# 12-MT7688AN_DDR2_I_F-B.net
KiCad netlist of a schematic drawn in Altium Designer
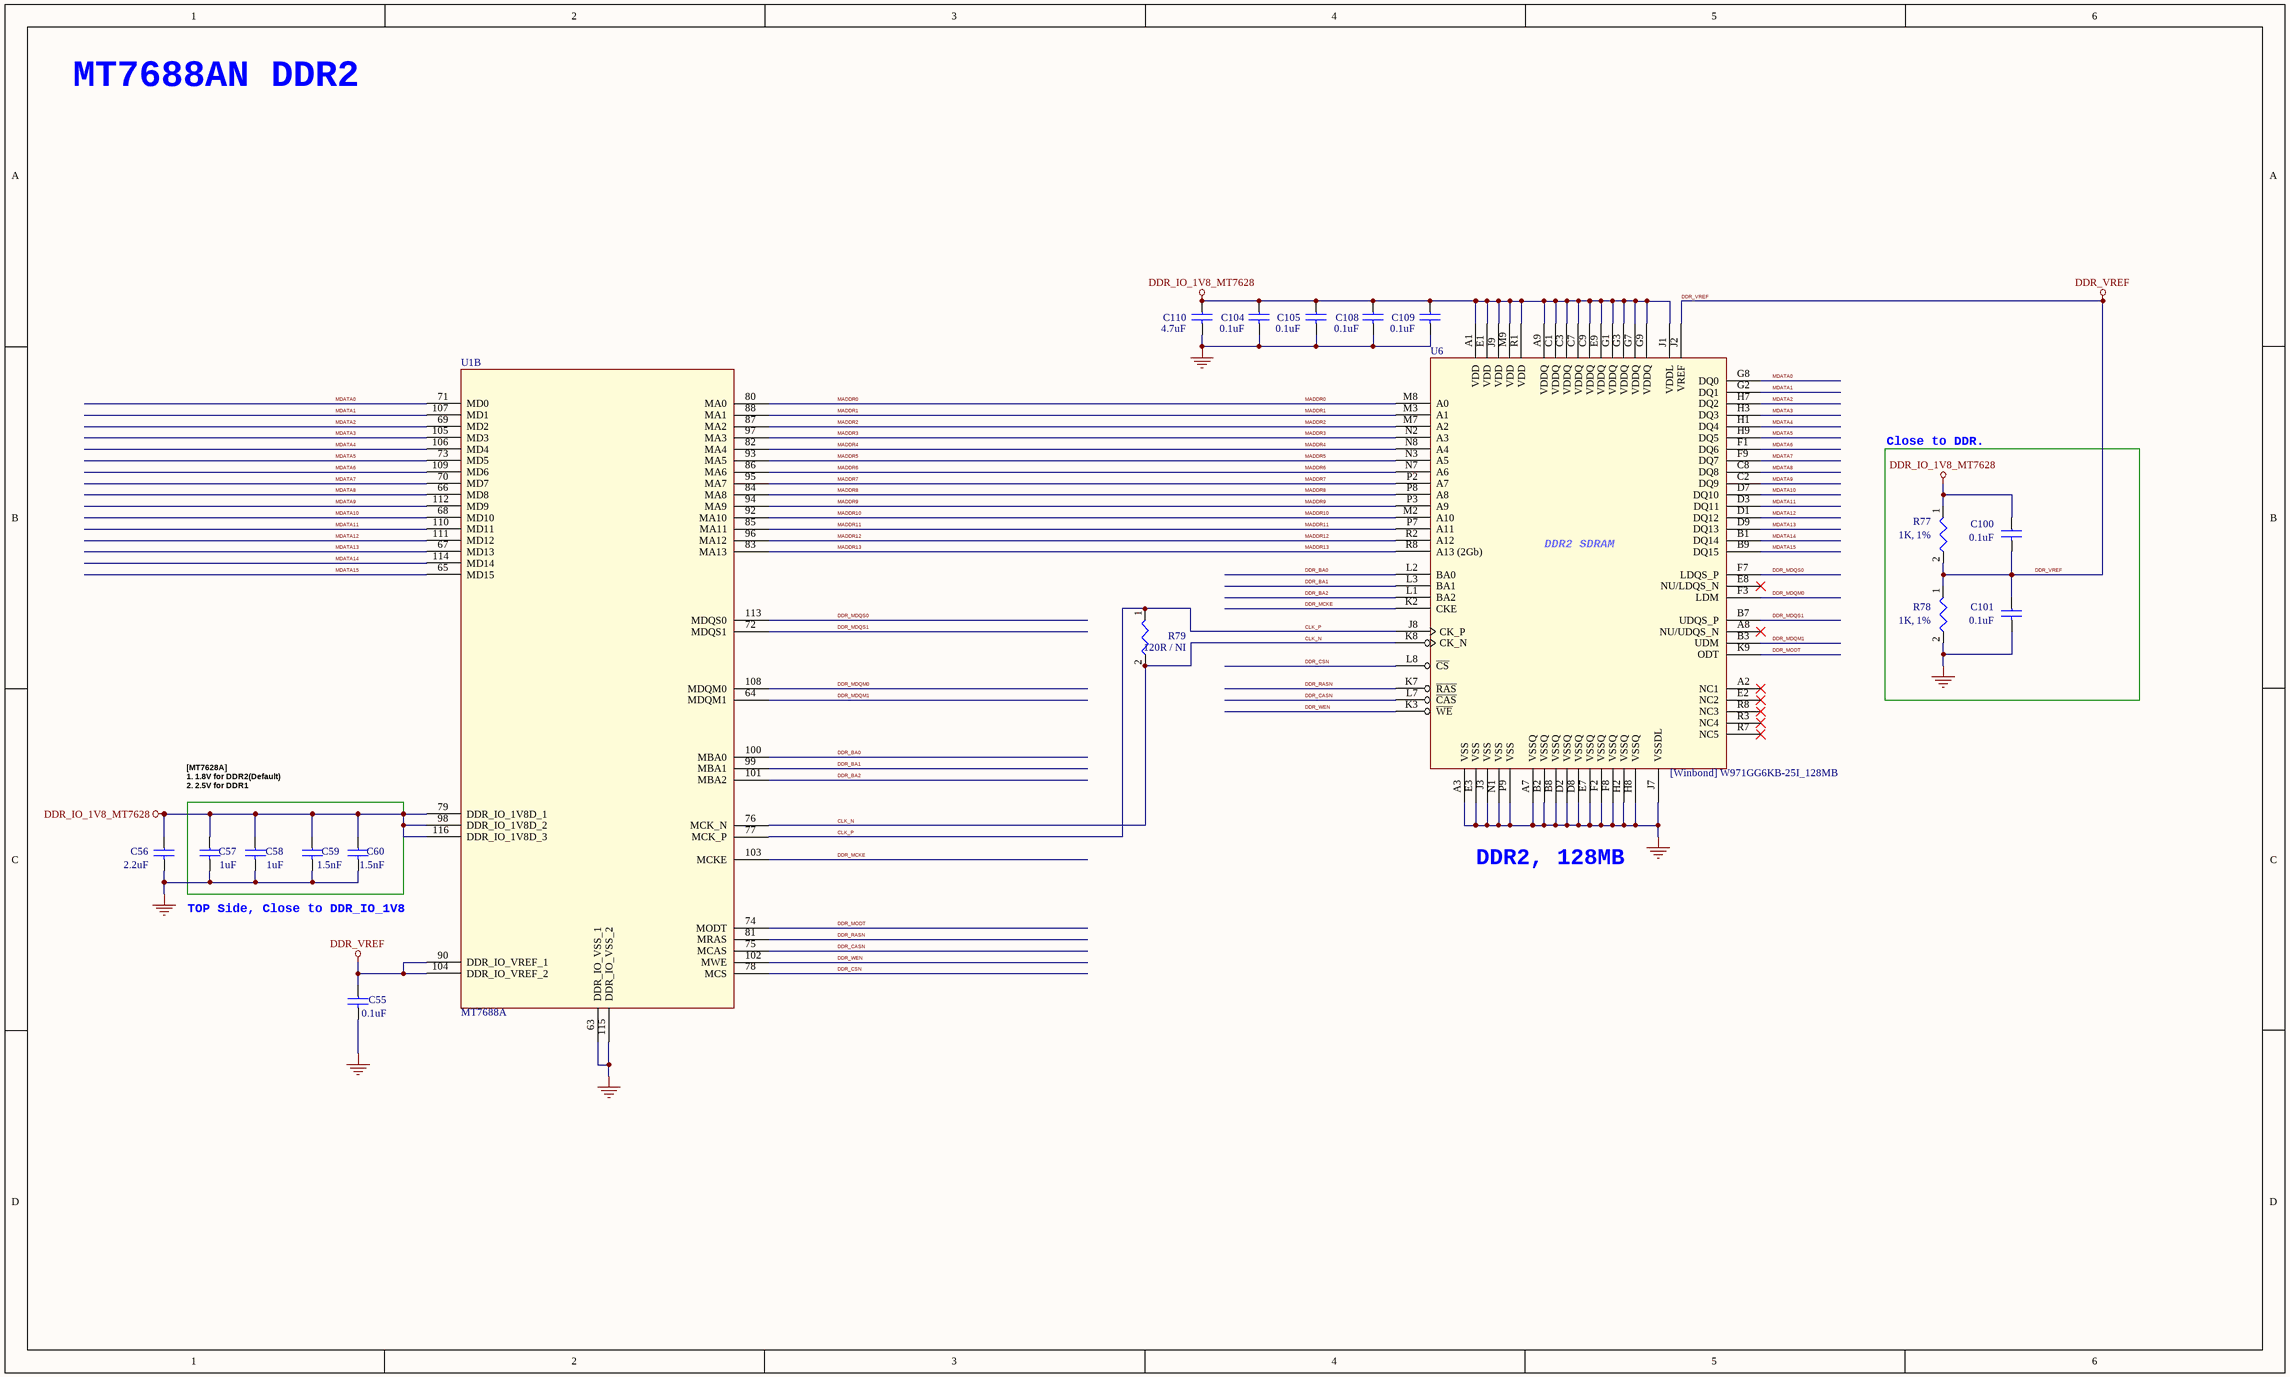
[diagram p0: 12-MT7688AN DDR2 I_F-B.SchDoc]

(export (version "E")
  (design (tool "Eeschema 10.0.6"))
  (components
    (comp (ref "C55")
      (value "0.1uF")
      (footprint "RLC 0201 M35")
      (libsource (lib "LinkIt Air+ (EK-7688AM+)") (part "CAP NP"))
    )
    (comp (ref "C56")
      (value "2.2uF")
      (footprint "RLC 0402 M35")
      (libsource (lib "LinkIt Air+ (EK-7688AM+)") (part "CAP NP"))
    )
    (comp (ref "C57")
      (value "1uF")
      (footprint "RLC 0201 M35")
      (libsource (lib "LinkIt Air+ (EK-7688AM+)") (part "CAP NP"))
    )
    (comp (ref "C58")
      (value "1uF")
      (footprint "RLC 0201 M35")
      (libsource (lib "LinkIt Air+ (EK-7688AM+)") (part "CAP NP"))
    )
    (comp (ref "C59")
      (value "1.5nF")
      (footprint "RLC 0201 M35")
      (libsource (lib "LinkIt Air+ (EK-7688AM+)") (part "CAP NP"))
    )
    (comp (ref "C60")
      (value "1.5nF")
      (footprint "RLC 0201 M35")
      (libsource (lib "LinkIt Air+ (EK-7688AM+)") (part "CAP NP"))
    )
    (comp (ref "C100")
      (value "0.1uF")
      (footprint "RLC 0201 M35")
      (libsource (lib "LinkIt Air+ (EK-7688AM+)") (part "CAP NP"))
    )
    (comp (ref "C101")
      (value "0.1uF")
      (footprint "RLC 0201 M35")
      (libsource (lib "LinkIt Air+ (EK-7688AM+)") (part "CAP NP"))
    )
    (comp (ref "C104")
      (value "0.1uF")
      (footprint "RLC 0201 M35")
      (libsource (lib "LinkIt Air+ (EK-7688AM+)") (part "CAP NP"))
    )
    (comp (ref "C105")
      (value "0.1uF")
      (footprint "RLC 0201 M35")
      (libsource (lib "LinkIt Air+ (EK-7688AM+)") (part "CAP NP"))
    )
    (comp (ref "C108")
      (value "0.1uF")
      (footprint "RLC 0201 M35")
      (libsource (lib "LinkIt Air+ (EK-7688AM+)") (part "CAP NP"))
    )
    (comp (ref "C109")
      (value "0.1uF")
      (footprint "RLC 0201 M35")
      (libsource (lib "LinkIt Air+ (EK-7688AM+)") (part "CAP NP"))
    )
    (comp (ref "C110")
      (value "4.7uF")
      (footprint "RLC 0402 M35")
      (libsource (lib "LinkIt Air+ (EK-7688AM+)") (part "CAP NP"))
    )
    (comp (ref "R77")
      (value "1K, 1%")
      (footprint "RLC 0201 M35")
      (libsource (lib "LinkIt Air+ (EK-7688AM+)") (part "RES/0402_3"))
    )
    (comp (ref "R78")
      (value "1K, 1%")
      (footprint "RLC 0201 M35")
      (libsource (lib "LinkIt Air+ (EK-7688AM+)") (part "RES/0402_3"))
    )
    (comp (ref "R79")
      (value "120R / NI")
      (footprint "RLC 0201 M35")
      (libsource (lib "LinkIt Air+ (EK-7688AM+)") (part "RES/0402_3"))
    )
    (comp (ref "U1")
      (value "MT7688A")
      (footprint "MT7628AN$2F$DRQFN156$2F$SMD$2F$P0.5$2F$12X12")
      (libsource (lib "LinkIt Air+ (EK-7688AM+)") (part "MT7620N-n_26"))
    )
    (comp (ref "U6")
      (value "[Winbond] W971GG6KB-25I_128MB")
      (footprint "BGA84C80P9X15_800X1250X120")
      (description "DDR2, 128MB")
      (libsource (lib "LinkIt Air+ (EK-7688AM+)") (part "W971GG6KB-25I"))
    )
  )
  (nets
    (net (code "1") (name "/CLK_N") (class "Default")
      (node (ref "R79") (pin "2") (pinfunction "2_2") (pintype "passive"))
      (node (ref "U1") (pin "76") (pinfunction "MCK_N_76") (pintype "passive"))
      (node (ref "U6") (pin "K8") (pinfunction "CK_N_K8") (pintype "passive"))
    )
    (net (code "2") (name "/CLK_P") (class "Default")
      (node (ref "R79") (pin "1") (pinfunction "1_1") (pintype "passive"))
      (node (ref "U1") (pin "77") (pinfunction "MCK_P_77") (pintype "passive"))
      (node (ref "U6") (pin "J8") (pinfunction "CK_P_J8") (pintype "passive"))
    )
    (net (code "3") (name "/DDR_BA0") (class "Default")
      (node (ref "U1") (pin "100") (pinfunction "MBA0_100") (pintype "passive"))
      (node (ref "U6") (pin "L2") (pinfunction "BA0_L2") (pintype "passive"))
    )
    (net (code "4") (name "/DDR_BA1") (class "Default")
      (node (ref "U1") (pin "99") (pinfunction "MBA1_99") (pintype "passive"))
      (node (ref "U6") (pin "L3") (pinfunction "BA1_L3") (pintype "passive"))
    )
    (net (code "5") (name "/DDR_BA2") (class "Default")
      (node (ref "U1") (pin "101") (pinfunction "MBA2_101") (pintype "passive"))
      (node (ref "U6") (pin "L1") (pinfunction "BA2_L1") (pintype "passive"))
    )
    (net (code "6") (name "/DDR_CASN") (class "Default")
      (node (ref "U1") (pin "75") (pinfunction "MCAS_75") (pintype "passive"))
      (node (ref "U6") (pin "L7") (pinfunction "~{CAS}_L7") (pintype "passive"))
    )
    (net (code "7") (name "/DDR_CSN") (class "Default")
      (node (ref "U1") (pin "78") (pinfunction "MCS_78") (pintype "passive"))
      (node (ref "U6") (pin "L8") (pinfunction "~{CS}_L8") (pintype "passive"))
    )
    (net (code "8") (name "/DDR_MCKE") (class "Default")
      (node (ref "U1") (pin "103") (pinfunction "MCKE_103") (pintype "passive"))
      (node (ref "U6") (pin "K2") (pinfunction "CKE_K2") (pintype "passive"))
    )
    (net (code "9") (name "/DDR_MDQM0") (class "Default")
      (node (ref "U1") (pin "108") (pinfunction "MDQM0_108") (pintype "passive"))
      (node (ref "U6") (pin "F3") (pinfunction "LDM_F3") (pintype "passive"))
    )
    (net (code "10") (name "/DDR_MDQM1") (class "Default")
      (node (ref "U1") (pin "64") (pinfunction "MDQM1_64") (pintype "passive"))
      (node (ref "U6") (pin "B3") (pinfunction "UDM_B3") (pintype "passive"))
    )
    (net (code "11") (name "/DDR_MDQS0") (class "Default")
      (node (ref "U1") (pin "113") (pinfunction "MDQS0_113") (pintype "passive"))
      (node (ref "U6") (pin "F7") (pinfunction "LDQS_P_F7") (pintype "passive"))
    )
    (net (code "12") (name "/DDR_MDQS1") (class "Default")
      (node (ref "U1") (pin "72") (pinfunction "MDQS1_72") (pintype "passive"))
      (node (ref "U6") (pin "B7") (pinfunction "UDQS_P_B7") (pintype "passive"))
    )
    (net (code "13") (name "/DDR_MODT") (class "Default")
      (node (ref "U1") (pin "74") (pinfunction "MODT_74") (pintype "passive"))
      (node (ref "U6") (pin "K9") (pinfunction "ODT_K9") (pintype "passive"))
    )
    (net (code "14") (name "/DDR_RASN") (class "Default")
      (node (ref "U1") (pin "81") (pinfunction "MRAS_81") (pintype "passive"))
      (node (ref "U6") (pin "K7") (pinfunction "~{RAS}_K7") (pintype "passive"))
    )
    (net (code "15") (name "/DDR_WEN") (class "Default")
      (node (ref "U1") (pin "102") (pinfunction "MWE_102") (pintype "passive"))
      (node (ref "U6") (pin "K3") (pinfunction "~{WE}_K3") (pintype "passive"))
    )
    (net (code "16") (name "/MADDR0") (class "Default")
      (node (ref "U1") (pin "80") (pinfunction "MA0_80") (pintype "passive"))
      (node (ref "U6") (pin "M8") (pinfunction "A0_M8") (pintype "passive"))
    )
    (net (code "17") (name "/MADDR1") (class "Default")
      (node (ref "U1") (pin "88") (pinfunction "MA1_88") (pintype "passive"))
      (node (ref "U6") (pin "M3") (pinfunction "A1_M3") (pintype "passive"))
    )
    (net (code "18") (name "/MADDR2") (class "Default")
      (node (ref "U1") (pin "87") (pinfunction "MA2_87") (pintype "passive"))
      (node (ref "U6") (pin "M7") (pinfunction "A2_M7") (pintype "passive"))
    )
    (net (code "19") (name "/MADDR3") (class "Default")
      (node (ref "U1") (pin "97") (pinfunction "MA3_97") (pintype "passive"))
      (node (ref "U6") (pin "N2") (pinfunction "A3_N2") (pintype "passive"))
    )
    (net (code "20") (name "/MADDR4") (class "Default")
      (node (ref "U1") (pin "82") (pinfunction "MA4_82") (pintype "passive"))
      (node (ref "U6") (pin "N8") (pinfunction "A4_N8") (pintype "passive"))
    )
    (net (code "21") (name "/MADDR5") (class "Default")
      (node (ref "U1") (pin "93") (pinfunction "MA5_93") (pintype "passive"))
      (node (ref "U6") (pin "N3") (pinfunction "A5_N3") (pintype "passive"))
    )
    (net (code "22") (name "/MADDR6") (class "Default")
      (node (ref "U1") (pin "86") (pinfunction "MA6_86") (pintype "passive"))
      (node (ref "U6") (pin "N7") (pinfunction "A6_N7") (pintype "passive"))
    )
    (net (code "23") (name "/MADDR7") (class "Default")
      (node (ref "U1") (pin "95") (pinfunction "MA7_95") (pintype "passive"))
      (node (ref "U6") (pin "P2") (pinfunction "A7_P2") (pintype "passive"))
    )
    (net (code "24") (name "/MADDR8") (class "Default")
      (node (ref "U1") (pin "84") (pinfunction "MA8_84") (pintype "passive"))
      (node (ref "U6") (pin "P8") (pinfunction "A8_P8") (pintype "passive"))
    )
    (net (code "25") (name "/MADDR9") (class "Default")
      (node (ref "U1") (pin "94") (pinfunction "MA9_94") (pintype "passive"))
      (node (ref "U6") (pin "P3") (pinfunction "A9_P3") (pintype "passive"))
    )
    (net (code "26") (name "/MADDR10") (class "Default")
      (node (ref "U1") (pin "92") (pinfunction "MA10_92") (pintype "passive"))
      (node (ref "U6") (pin "M2") (pinfunction "A10_M2") (pintype "passive"))
    )
    (net (code "27") (name "/MADDR11") (class "Default")
      (node (ref "U1") (pin "85") (pinfunction "MA11_85") (pintype "passive"))
      (node (ref "U6") (pin "P7") (pinfunction "A11_P7") (pintype "passive"))
    )
    (net (code "28") (name "/MADDR12") (class "Default")
      (node (ref "U1") (pin "96") (pinfunction "MA12_96") (pintype "passive"))
      (node (ref "U6") (pin "R2") (pinfunction "A12_R2") (pintype "passive"))
    )
    (net (code "29") (name "/MADDR13") (class "Default")
      (node (ref "U1") (pin "83") (pinfunction "MA13_83") (pintype "passive"))
      (node (ref "U6") (pin "R8") (pinfunction "A13_(2Gb)_R8") (pintype "passive"))
    )
    (net (code "30") (name "/MDATA0") (class "Default")
      (node (ref "U1") (pin "71") (pinfunction "MD0_71") (pintype "passive"))
      (node (ref "U6") (pin "G8") (pinfunction "DQ0_G8") (pintype "passive"))
    )
    (net (code "31") (name "/MDATA1") (class "Default")
      (node (ref "U1") (pin "107") (pinfunction "MD1_107") (pintype "passive"))
      (node (ref "U6") (pin "G2") (pinfunction "DQ1_G2") (pintype "passive"))
    )
    (net (code "32") (name "/MDATA2") (class "Default")
      (node (ref "U1") (pin "69") (pinfunction "MD2_69") (pintype "passive"))
      (node (ref "U6") (pin "H7") (pinfunction "DQ2_H7") (pintype "passive"))
    )
    (net (code "33") (name "/MDATA3") (class "Default")
      (node (ref "U1") (pin "105") (pinfunction "MD3_105") (pintype "passive"))
      (node (ref "U6") (pin "H3") (pinfunction "DQ3_H3") (pintype "passive"))
    )
    (net (code "34") (name "/MDATA4") (class "Default")
      (node (ref "U1") (pin "106") (pinfunction "MD4_106") (pintype "passive"))
      (node (ref "U6") (pin "H1") (pinfunction "DQ4_H1") (pintype "passive"))
    )
    (net (code "35") (name "/MDATA5") (class "Default")
      (node (ref "U1") (pin "73") (pinfunction "MD5_73") (pintype "passive"))
      (node (ref "U6") (pin "H9") (pinfunction "DQ5_H9") (pintype "passive"))
    )
    (net (code "36") (name "/MDATA6") (class "Default")
      (node (ref "U1") (pin "109") (pinfunction "MD6_109") (pintype "passive"))
      (node (ref "U6") (pin "F1") (pinfunction "DQ6_F1") (pintype "passive"))
    )
    (net (code "37") (name "/MDATA7") (class "Default")
      (node (ref "U1") (pin "70") (pinfunction "MD7_70") (pintype "passive"))
      (node (ref "U6") (pin "F9") (pinfunction "DQ7_F9") (pintype "passive"))
    )
    (net (code "38") (name "/MDATA8") (class "Default")
      (node (ref "U1") (pin "66") (pinfunction "MD8_66") (pintype "passive"))
      (node (ref "U6") (pin "C8") (pinfunction "DQ8_C8") (pintype "passive"))
    )
    (net (code "39") (name "/MDATA9") (class "Default")
      (node (ref "U1") (pin "112") (pinfunction "MD9_112") (pintype "passive"))
      (node (ref "U6") (pin "C2") (pinfunction "DQ9_C2") (pintype "passive"))
    )
    (net (code "40") (name "/MDATA10") (class "Default")
      (node (ref "U1") (pin "68") (pinfunction "MD10_68") (pintype "passive"))
      (node (ref "U6") (pin "D7") (pinfunction "DQ10_D7") (pintype "passive"))
    )
    (net (code "41") (name "/MDATA11") (class "Default")
      (node (ref "U1") (pin "110") (pinfunction "MD11_110") (pintype "passive"))
      (node (ref "U6") (pin "D3") (pinfunction "DQ11_D3") (pintype "passive"))
    )
    (net (code "42") (name "/MDATA12") (class "Default")
      (node (ref "U1") (pin "111") (pinfunction "MD12_111") (pintype "passive"))
      (node (ref "U6") (pin "D1") (pinfunction "DQ12_D1") (pintype "passive"))
    )
    (net (code "43") (name "/MDATA13") (class "Default")
      (node (ref "U1") (pin "67") (pinfunction "MD13_67") (pintype "passive"))
      (node (ref "U6") (pin "D9") (pinfunction "DQ13_D9") (pintype "passive"))
    )
    (net (code "44") (name "/MDATA14") (class "Default")
      (node (ref "U1") (pin "114") (pinfunction "MD14_114") (pintype "passive"))
      (node (ref "U6") (pin "B1") (pinfunction "DQ14_B1") (pintype "passive"))
    )
    (net (code "45") (name "/MDATA15") (class "Default")
      (node (ref "U1") (pin "65") (pinfunction "MD15_65") (pintype "passive"))
      (node (ref "U6") (pin "B9") (pinfunction "DQ15_B9") (pintype "passive"))
    )
    (net (code "46") (name "DDR_IO_1V8_MT7628") (class "Default")
      (node (ref "C100") (pin "1") (pinfunction "1_1") (pintype "passive"))
      (node (ref "C104") (pin "1") (pinfunction "1_1") (pintype "passive"))
      (node (ref "C105") (pin "1") (pinfunction "1_1") (pintype "passive"))
      (node (ref "C108") (pin "1") (pinfunction "1_1") (pintype "passive"))
      (node (ref "C109") (pin "1") (pinfunction "1_1") (pintype "passive"))
      (node (ref "C110") (pin "1") (pinfunction "1_1") (pintype "passive"))
      (node (ref "C56") (pin "1") (pinfunction "1_1") (pintype "passive"))
      (node (ref "C57") (pin "1") (pinfunction "1_1") (pintype "passive"))
      (node (ref "C58") (pin "1") (pinfunction "1_1") (pintype "passive"))
      (node (ref "C59") (pin "1") (pinfunction "1_1") (pintype "passive"))
      (node (ref "C60") (pin "1") (pinfunction "1_1") (pintype "passive"))
      (node (ref "R77") (pin "1") (pinfunction "1_1") (pintype "passive"))
      (node (ref "U1") (pin "116") (pinfunction "DDR_IO_1V8D_3_116") (pintype "power_in"))
      (node (ref "U1") (pin "79") (pinfunction "DDR_IO_1V8D_1_79") (pintype "power_in"))
      (node (ref "U1") (pin "98") (pinfunction "DDR_IO_1V8D_2_98") (pintype "power_in"))
      (node (ref "U6") (pin "A1") (pinfunction "VDD_A1") (pintype "power_in"))
      (node (ref "U6") (pin "A9") (pinfunction "VDDQ_A9") (pintype "power_in"))
      (node (ref "U6") (pin "C1") (pinfunction "VDDQ_C1") (pintype "power_in"))
      (node (ref "U6") (pin "C3") (pinfunction "VDDQ_C3") (pintype "power_in"))
      (node (ref "U6") (pin "C7") (pinfunction "VDDQ_C7") (pintype "power_in"))
      (node (ref "U6") (pin "C9") (pinfunction "VDDQ_C9") (pintype "power_in"))
      (node (ref "U6") (pin "E1") (pinfunction "VDD_E1") (pintype "power_in"))
      (node (ref "U6") (pin "E9") (pinfunction "VDDQ_E9") (pintype "power_in"))
      (node (ref "U6") (pin "G1") (pinfunction "VDDQ_G1") (pintype "power_in"))
      (node (ref "U6") (pin "G3") (pinfunction "VDDQ_G3") (pintype "power_in"))
      (node (ref "U6") (pin "G7") (pinfunction "VDDQ_G7") (pintype "power_in"))
      (node (ref "U6") (pin "G9") (pinfunction "VDDQ_G9") (pintype "power_in"))
      (node (ref "U6") (pin "J1") (pinfunction "VDDL_J1") (pintype "power_in"))
      (node (ref "U6") (pin "J9") (pinfunction "VDD_J9") (pintype "power_in"))
      (node (ref "U6") (pin "M9") (pinfunction "VDD_M9") (pintype "power_in"))
      (node (ref "U6") (pin "R1") (pinfunction "VDD_R1") (pintype "power_in"))
    )
    (net (code "47") (name "DDR_VREF") (class "Default")
      (node (ref "C100") (pin "2") (pinfunction "2_2") (pintype "passive"))
      (node (ref "C101") (pin "1") (pinfunction "1_1") (pintype "passive"))
      (node (ref "C55") (pin "1") (pinfunction "1_1") (pintype "passive"))
      (node (ref "R77") (pin "2") (pinfunction "2_2") (pintype "passive"))
      (node (ref "R78") (pin "1") (pinfunction "1_1") (pintype "passive"))
      (node (ref "U1") (pin "104") (pinfunction "DDR_IO_VREF_2_104") (pintype "power_in"))
      (node (ref "U1") (pin "90") (pinfunction "DDR_IO_VREF_1_90") (pintype "power_in"))
      (node (ref "U6") (pin "J2") (pinfunction "VREF_J2") (pintype "power_in"))
    )
    (net (code "48") (name "GND") (class "Default")
      (node (ref "C101") (pin "2") (pinfunction "2_2") (pintype "passive"))
      (node (ref "C104") (pin "2") (pinfunction "2_2") (pintype "passive"))
      (node (ref "C105") (pin "2") (pinfunction "2_2") (pintype "passive"))
      (node (ref "C108") (pin "2") (pinfunction "2_2") (pintype "passive"))
      (node (ref "C109") (pin "2") (pinfunction "2_2") (pintype "passive"))
      (node (ref "C110") (pin "2") (pinfunction "2_2") (pintype "passive"))
      (node (ref "C55") (pin "2") (pinfunction "2_2") (pintype "passive"))
      (node (ref "C56") (pin "2") (pinfunction "2_2") (pintype "passive"))
      (node (ref "C57") (pin "2") (pinfunction "2_2") (pintype "passive"))
      (node (ref "C58") (pin "2") (pinfunction "2_2") (pintype "passive"))
      (node (ref "C59") (pin "2") (pinfunction "2_2") (pintype "passive"))
      (node (ref "C60") (pin "2") (pinfunction "2_2") (pintype "passive"))
      (node (ref "R78") (pin "2") (pinfunction "2_2") (pintype "passive"))
      (node (ref "U1") (pin "115") (pinfunction "DDR_IO_VSS_2_115") (pintype "passive"))
      (node (ref "U1") (pin "63") (pinfunction "DDR_IO_VSS_1_63") (pintype "power_in"))
      (node (ref "U6") (pin "A3") (pinfunction "VSS_A3") (pintype "power_in"))
      (node (ref "U6") (pin "A7") (pinfunction "VSSQ_A7") (pintype "power_in"))
      (node (ref "U6") (pin "B2") (pinfunction "VSSQ_B2") (pintype "power_in"))
      (node (ref "U6") (pin "B8") (pinfunction "VSSQ_B8") (pintype "power_in"))
      (node (ref "U6") (pin "D2") (pinfunction "VSSQ_D2") (pintype "power_in"))
      (node (ref "U6") (pin "D8") (pinfunction "VSSQ_D8") (pintype "power_in"))
      (node (ref "U6") (pin "E3") (pinfunction "VSS_E3") (pintype "power_in"))
      (node (ref "U6") (pin "E7") (pinfunction "VSSQ_E7") (pintype "power_in"))
      (node (ref "U6") (pin "F2") (pinfunction "VSSQ_F2") (pintype "power_in"))
      (node (ref "U6") (pin "F8") (pinfunction "VSSQ_F8") (pintype "power_in"))
      (node (ref "U6") (pin "H2") (pinfunction "VSSQ_H2") (pintype "power_in"))
      (node (ref "U6") (pin "H8") (pinfunction "VSSQ_H8") (pintype "power_in"))
      (node (ref "U6") (pin "J3") (pinfunction "VSS_J3") (pintype "power_in"))
      (node (ref "U6") (pin "J7") (pinfunction "VSSDL_J7") (pintype "power_in"))
      (node (ref "U6") (pin "N1") (pinfunction "VSS_N1") (pintype "power_in"))
      (node (ref "U6") (pin "P9") (pinfunction "VSS_P9") (pintype "power_in"))
    )
    (net (code "49") (name "unconnected-(U6-NC1-PadA2)") (class "Default")
      (node (ref "U6") (pin "A2") (pinfunction "NC1_A2") (pintype "passive+no_connect"))
    )
    (net (code "50") (name "unconnected-(U6-NC2-PadE2)") (class "Default")
      (node (ref "U6") (pin "E2") (pinfunction "NC2_E2") (pintype "passive+no_connect"))
    )
    (net (code "51") (name "unconnected-(U6-NC3-PadR8)") (class "Default")
      (node (ref "U6") (pin "R8") (pinfunction "NC3_R8") (pintype "passive+no_connect"))
    )
    (net (code "52") (name "unconnected-(U6-NC4-PadR3)") (class "Default")
      (node (ref "U6") (pin "R3") (pinfunction "NC4_R3") (pintype "passive+no_connect"))
    )
    (net (code "53") (name "unconnected-(U6-NC5-PadR7)") (class "Default")
      (node (ref "U6") (pin "R7") (pinfunction "NC5_R7") (pintype "passive+no_connect"))
    )
    (net (code "54") (name "unconnected-(U6-NU{slash}LDQS_N-PadE8)") (class "Default")
      (node (ref "U6") (pin "E8") (pinfunction "NU/LDQS_N_E8") (pintype "passive+no_connect"))
    )
    (net (code "55") (name "unconnected-(U6-NU{slash}UDQS_N-PadA8)") (class "Default")
      (node (ref "U6") (pin "A8") (pinfunction "NU/UDQS_N_A8") (pintype "passive+no_connect"))
    )
  )
)
